# Solenoids.net
KiCad netlist of a schematic drawn in Altium Designer
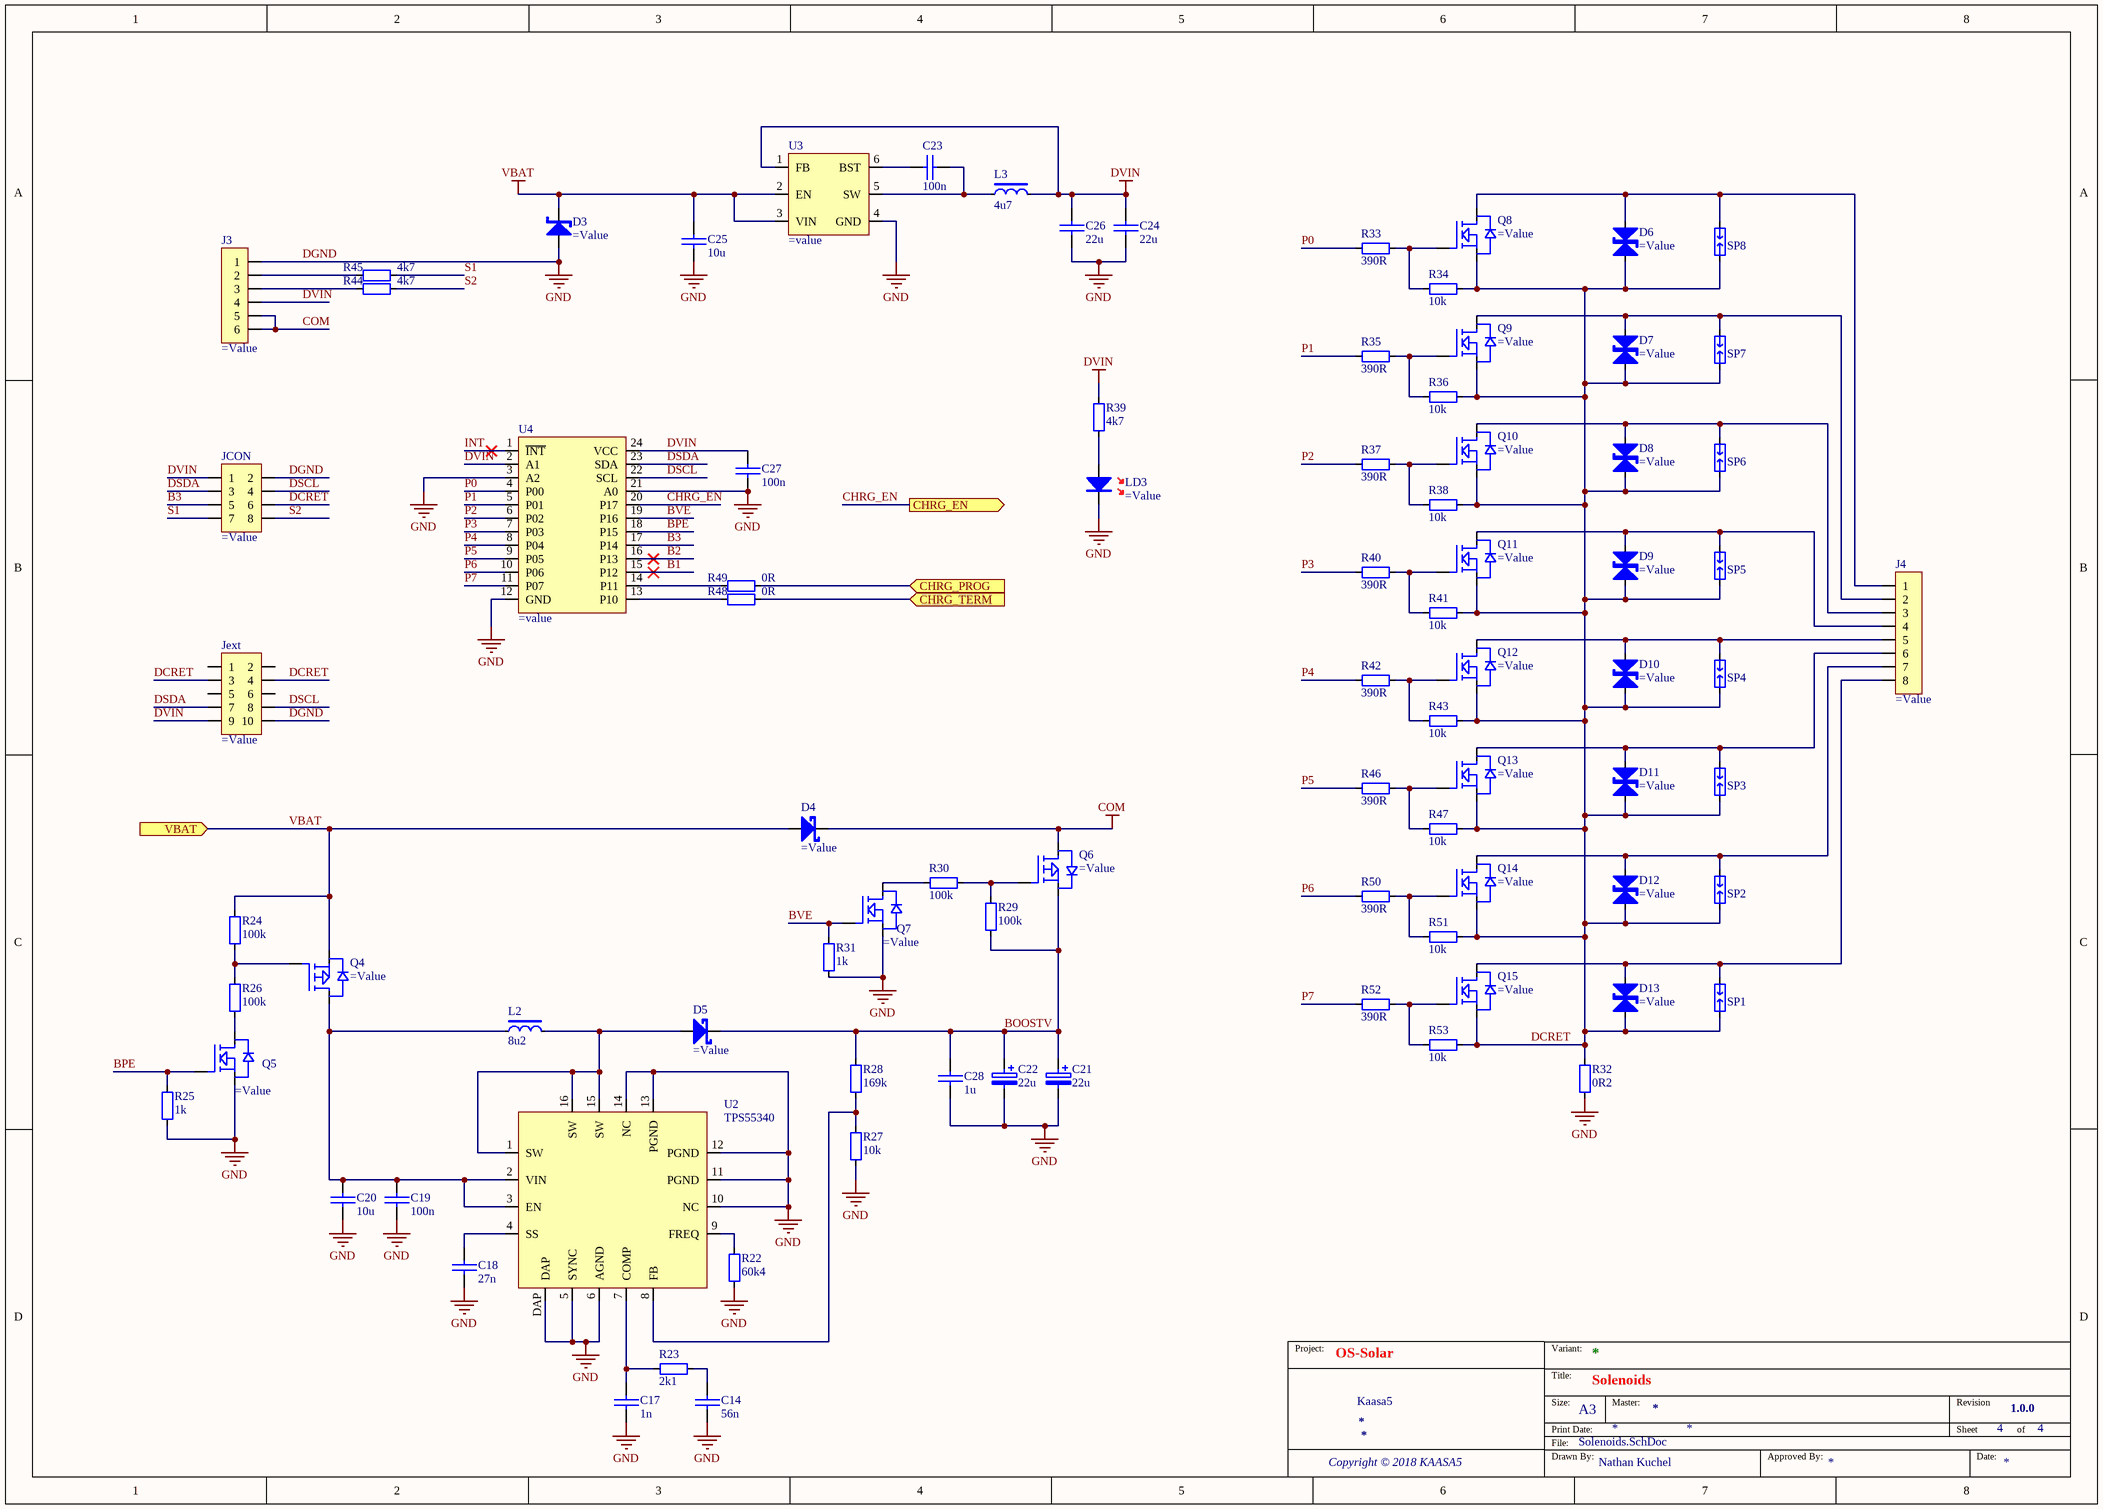
[diagram p0: Solenoids.SchDoc]

(export (version "E")
  (design (tool "Eeschema 10.0.6"))
  (components
    (comp (ref "C14")
      (value "56n")
      (footprint "CAPC1608X09N")
      (description "CAP SMD CER X7R 5% 50V 0603 (1608 Metric)")
      (fields (field (name "MANUFACTURER") "AVX Corporation") (field (name "PART NUMBER") "06035C563JAT2A"))
      (libsource (lib "kaasa5") (part "C_NORM"))
    )
    (comp (ref "C17")
      (value "1n")
      (footprint "CAPC1608X09N")
      (description "CAP SMD CER C0G/NPO 5% 50V 0603 (1608 Metric)")
      (fields (field (name "MANUFACTURER") "Yageo") (field (name "PART NUMBER") "CC0603JRNPO9BN102"))
      (libsource (lib "kaasa5") (part "C_NORM"))
    )
    (comp (ref "C18")
      (value "27n")
      (footprint "CAPC1608X09N")
      (description "CAP SMD CER X7R 5% 50V 0603 (1608 Metric)")
      (fields (field (name "MANUFACTURER") "Yageo") (field (name "PART NUMBER") "CC0603JRX7R9BB273"))
      (libsource (lib "kaasa5") (part "C_NORM"))
    )
    (comp (ref "C19")
      (value "100n")
      (footprint "CAPC1608X09N")
      (description "CAP SMD CER X7R 10% 50V 0603 (1608 Metric)")
      (fields (field (name "MANUFACTURER") "Yageo") (field (name "PART NUMBER") "CC0603KRX7R9BB104"))
      (libsource (lib "kaasa5") (part "C_NORM"))
    )
    (comp (ref "C20")
      (value "10u")
      (footprint "CAPC3216X18N")
      (description "CAP SMD CER X7R 10% 50V 1206 (3216 Metric)")
      (fields
        (field (name "MANUFACTURER") "Samsung Electro-Mechanics")
        (field (name "PART NUMBER") "CL31B106KBHNNNE")
      )
      (libsource (lib "kaasa5") (part "C_NORM"))
    )
    (comp (ref "C21")
      (value "22u")
      (footprint "CAPAE630X600")
      (description "CAP SMD ELECTRO 20% 35V SMAE")
      (fields
        (field (name "MANUFACTURER") "Panasonic Electronic Components")
        (field (name "PART NUMBER") "35SVPF22M")
      )
      (libsource (lib "kaasa5") (part "C_POL"))
    )
    (comp (ref "C22")
      (value "22u")
      (footprint "CAPAE630X600")
      (description "CAP SMD ELECTRO 20% 35V SMAE")
      (fields
        (field (name "MANUFACTURER") "Panasonic Electronic Components")
        (field (name "PART NUMBER") "35SVPF22M")
      )
      (libsource (lib "kaasa5") (part "C_POL"))
    )
    (comp (ref "C23")
      (value "100n")
      (footprint "CAPC1608X09N")
      (description "CAP SMD CER X7R 10% 50V 0603 (1608 Metric)")
      (fields (field (name "MANUFACTURER") "Yageo") (field (name "PART NUMBER") "CC0603KRX7R9BB104"))
      (libsource (lib "kaasa5") (part "C_NORM"))
    )
    (comp (ref "C24")
      (value "22u")
      (footprint "CAPC3216X18N")
      (description "CAP SMD CER X7R 10% 10V 1206 (3216 Metric)")
      (fields
        (field (name "MANUFACTURER") "Samsung Electro-Mechanics")
        (field (name "PART NUMBER") "CL31B226KPHNNNE")
      )
      (libsource (lib "kaasa5") (part "C_NORM"))
    )
    (comp (ref "C25")
      (value "10u")
      (footprint "CAPC3216X18N")
      (description "CAP SMD CER X7R 10% 50V 1206 (3216 Metric)")
      (fields
        (field (name "MANUFACTURER") "Samsung Electro-Mechanics")
        (field (name "PART NUMBER") "CL31B106KBHNNNE")
      )
      (libsource (lib "kaasa5") (part "C_NORM"))
    )
    (comp (ref "C26")
      (value "22u")
      (footprint "CAPC3216X18N")
      (description "CAP SMD CER X7R 10% 10V 1206 (3216 Metric)")
      (fields
        (field (name "MANUFACTURER") "Samsung Electro-Mechanics")
        (field (name "PART NUMBER") "CL31B226KPHNNNE")
      )
      (libsource (lib "kaasa5") (part "C_NORM"))
    )
    (comp (ref "C27")
      (value "100n")
      (footprint "CAPC1608X09N")
      (description "CAP SMD CER X7R 10% 50V 0603 (1608 Metric)")
      (fields (field (name "MANUFACTURER") "Yageo") (field (name "PART NUMBER") "CC0603KRX7R9BB104"))
      (libsource (lib "kaasa5") (part "C_NORM"))
    )
    (comp (ref "C28")
      (value "1u")
      (footprint "CAPC1608X09N")
      (description "CAP SMD CER X7R 10% 50V 0805 (2012 Metric)")
      (fields (field (name "MANUFACTURER") "Yageo") (field (name "PART NUMBER") "CC0805KKX7R9BB105"))
      (libsource (lib "kaasa5") (part "C_NORM"))
    )
    (comp (ref "D3")
      (value "~")
      (footprint "DIOSMBX25N")
      (description "DIODE SMD TVS 24V 600W SMB")
      (fields (field (name "MANUFACTURER") "Littelfuse Inc.") (field (name "PART NUMBER") "SMBJ24A"))
      (libsource (lib "kaasa5") (part "ZD_NORM"))
    )
    (comp (ref "D4")
      (value "~")
      (footprint "DIOSMCX25N")
      (description "DIODE SMD SCHOTTKY 40V 3A SMC")
      (fields (field (name "MANUFACTURER") "ON Semiconductor") (field (name "PART NUMBER") "MBRS340T3G"))
      (libsource (lib "kaasa5") (part "D_SCHOTTKY"))
    )
    (comp (ref "D5")
      (value "~")
      (footprint "DIOSMCX25N")
      (description "DIODE SMD SCHOTTKY 40V 3A SMC")
      (fields (field (name "MANUFACTURER") "ON Semiconductor") (field (name "PART NUMBER") "MBRS340T3G"))
      (libsource (lib "kaasa5") (part "D_SCHOTTKY"))
    )
    (comp (ref "D6")
      (value "~")
      (footprint "DIOSMBX25NB")
      (description "DIODE SMD TVS 24V 600W SMB")
      (fields (field (name "MANUFACTURER") "Littelfuse Inc.") (field (name "PART NUMBER") "SMBJ24CA"))
      (libsource (lib "kaasa5") (part "D_TRANSORB"))
    )
    (comp (ref "D7")
      (value "~")
      (footprint "DIOSMBX25NB")
      (description "DIODE SMD TVS 24V 600W SMB")
      (fields (field (name "MANUFACTURER") "Littelfuse Inc.") (field (name "PART NUMBER") "SMBJ24CA"))
      (libsource (lib "kaasa5") (part "D_TRANSORB"))
    )
    (comp (ref "D8")
      (value "~")
      (footprint "DIOSMBX25NB")
      (description "DIODE SMD TVS 24V 600W SMB")
      (fields (field (name "MANUFACTURER") "Littelfuse Inc.") (field (name "PART NUMBER") "SMBJ24CA"))
      (libsource (lib "kaasa5") (part "D_TRANSORB"))
    )
    (comp (ref "D9")
      (value "~")
      (footprint "DIOSMBX25NB")
      (description "DIODE SMD TVS 24V 600W SMB")
      (fields (field (name "MANUFACTURER") "Littelfuse Inc.") (field (name "PART NUMBER") "SMBJ24CA"))
      (libsource (lib "kaasa5") (part "D_TRANSORB"))
    )
    (comp (ref "D10")
      (value "~")
      (footprint "DIOSMBX25NB")
      (description "DIODE SMD TVS 24V 600W SMB")
      (fields (field (name "MANUFACTURER") "Littelfuse Inc.") (field (name "PART NUMBER") "SMBJ24CA"))
      (libsource (lib "kaasa5") (part "D_TRANSORB"))
    )
    (comp (ref "D11")
      (value "~")
      (footprint "DIOSMBX25NB")
      (description "DIODE SMD TVS 24V 600W SMB")
      (fields (field (name "MANUFACTURER") "Littelfuse Inc.") (field (name "PART NUMBER") "SMBJ24CA"))
      (libsource (lib "kaasa5") (part "D_TRANSORB"))
    )
    (comp (ref "D12")
      (value "~")
      (footprint "DIOSMBX25NB")
      (description "DIODE SMD TVS 24V 600W SMB")
      (fields (field (name "MANUFACTURER") "Littelfuse Inc.") (field (name "PART NUMBER") "SMBJ24CA"))
      (libsource (lib "kaasa5") (part "D_TRANSORB"))
    )
    (comp (ref "D13")
      (value "~")
      (footprint "DIOSMBX25NB")
      (description "DIODE SMD TVS 24V 600W SMB")
      (fields (field (name "MANUFACTURER") "Littelfuse Inc.") (field (name "PART NUMBER") "SMBJ24CA"))
      (libsource (lib "kaasa5") (part "D_TRANSORB"))
    )
    (comp (ref "J3")
      (value "~")
      (footprint "HDR1X6_350_RA")
      (description "CON THRU RIGHT ANGLE 8A 300V Header 1x6pin")
      (fields (field (name "MANUFACTURER") "Molex, LLC") (field (name "PART NUMBER") "0395021006"))
      (libsource (lib "kaasa5") (part "J_CON_SIL_6"))
    )
    (comp (ref "J4")
      (value "~")
      (footprint "HDR1X8_350_RA")
      (description "CON THRU RIGHT ANGLE 8A 300V Header 1x8pin")
      (fields (field (name "MANUFACTURER") "Molex, LLC") (field (name "PART NUMBER") "0395021008"))
      (libsource (lib "kaasa5") (part "J_CON_SIL_8"))
    )
    (comp (ref "JCON")
      (value "~")
      (footprint "HDR2X4")
      (description "CON THRU VERTICAL 0.100\" (2.54mm)  Header 2x4pin")
      (fields
        (field (name "MANUFACTURER") "Amphenol Commercial Products")
        (field (name "PART NUMBER") "68602-208HLF")
      )
      (libsource (lib "kaasa5") (part "J_CON_IDC_8"))
    )
    (comp (ref "Jext")
      (value "~")
      (footprint "HDR2X5RA")
      (description "CON THRU RIGHT ANGLE 2.54mm 3A 250V Header 2x5pin")
      (fields
        (field (name "MANUFACTURER") "Wurth Electronics Inc")
        (field (name "PART NUMBER") "61201021721")
      )
      (libsource (lib "kaasa5") (part "J_CON_IDC_10"))
    )
    (comp (ref "L2")
      (value "8u2")
      (footprint "INDP5553X51N")
      (description "IND SMD Shielded W/W 20% 60V 5.6A 31.75mOhm 5553")
      (fields (field (name "MANUFACTURER") "Coilcraft") (field (name "PART NUMBER") "XAL5050-822MEB"))
      (libsource (lib "") (part "L_FER_1"))
    )
    (comp (ref "L3")
      (value "4u7")
      (footprint "INDP3030X15N")
      (description "IND SMD Shielded W/W 20% 1.4A 167mOhm 3015")
      (fields (field (name "MANUFACTURER") "Coilcraft") (field (name "PART NUMBER") "EPL3015-472MLB"))
      (libsource (lib "kaasa5") (part "L_FER"))
    )
    (comp (ref "LD3")
      (value "~")
      (footprint "LEDC1608X06N-RED")
      (description "LED SMD RED 180mcd Max 0603 (1608 Metric)")
      (fields (field (name "MANUFACTURER") "Lite-On Inc.") (field (name "PART NUMBER") "LTST-C191KRKT"))
      (libsource (lib "kaasa5") (part "LED_NORM_RED"))
    )
    (comp (ref "Q4")
      (value "~")
      (footprint "SOT95P230X110-3N")
      (description "TRANS MOSFET P-Channel -30V -4.3A 70mOhm SOT23")
      (fields (field (name "MANUFACTURER") "Diodes Incorporated") (field (name "PART NUMBER") "DMP3056L-7"))
      (libsource (lib "kaasa5") (part "Q_MOSFET_P_E"))
    )
    (comp (ref "Q5")
      (value "~")
      (footprint "SOT95P230X110-3N")
      (description "TRANS MOSFET N-Channel 60V 360mA SOT23")
      (fields (field (name "MANUFACTURER") "Nexperia USA Inc.") (field (name "PART NUMBER") "2N7002P,235"))
      (libsource (lib "kaasa5") (part "Q_MOSFET_N_E"))
    )
    (comp (ref "Q6")
      (value "~")
      (footprint "SOT95P230X110-3N")
      (description "TRANS MOSFET P-Channel -30V -4.3A 70mOhm SOT23")
      (fields (field (name "MANUFACTURER") "Diodes Incorporated") (field (name "PART NUMBER") "DMP3056L-7"))
      (libsource (lib "kaasa5") (part "Q_MOSFET_P_E"))
    )
    (comp (ref "Q7")
      (value "~")
      (footprint "SOT95P230X110-3N")
      (description "TRANS MOSFET N-Channel 60V 360mA SOT23")
      (fields (field (name "MANUFACTURER") "Nexperia USA Inc.") (field (name "PART NUMBER") "2N7002P,235"))
      (libsource (lib "kaasa5") (part "Q_MOSFET_N_E"))
    )
    (comp (ref "Q8")
      (value "~")
      (footprint "SOT95P230X110-3N")
      (description "TRANS MOSFET N-Channel 30V 5.6A 32mOhm SOT23")
      (fields (field (name "MANUFACTURER") "Diodes Incorporated") (field (name "PART NUMBER") "DMN3042L-7"))
      (libsource (lib "kaasa5") (part "Q_MOSFET_N_E"))
    )
    (comp (ref "Q9")
      (value "~")
      (footprint "SOT95P230X110-3N")
      (description "TRANS MOSFET N-Channel 30V 5.6A 32mOhm SOT23")
      (fields (field (name "MANUFACTURER") "Diodes Incorporated") (field (name "PART NUMBER") "DMN3042L-7"))
      (libsource (lib "kaasa5") (part "Q_MOSFET_N_E"))
    )
    (comp (ref "Q10")
      (value "~")
      (footprint "SOT95P230X110-3N")
      (description "TRANS MOSFET N-Channel 30V 5.6A 32mOhm SOT23")
      (fields (field (name "MANUFACTURER") "Diodes Incorporated") (field (name "PART NUMBER") "DMN3042L-7"))
      (libsource (lib "kaasa5") (part "Q_MOSFET_N_E"))
    )
    (comp (ref "Q11")
      (value "~")
      (footprint "SOT95P230X110-3N")
      (description "TRANS MOSFET N-Channel 30V 5.6A 32mOhm SOT23")
      (fields (field (name "MANUFACTURER") "Diodes Incorporated") (field (name "PART NUMBER") "DMN3042L-7"))
      (libsource (lib "kaasa5") (part "Q_MOSFET_N_E"))
    )
    (comp (ref "Q12")
      (value "~")
      (footprint "SOT95P230X110-3N")
      (description "TRANS MOSFET N-Channel 30V 5.6A 32mOhm SOT23")
      (fields (field (name "MANUFACTURER") "Diodes Incorporated") (field (name "PART NUMBER") "DMN3042L-7"))
      (libsource (lib "kaasa5") (part "Q_MOSFET_N_E"))
    )
    (comp (ref "Q13")
      (value "~")
      (footprint "SOT95P230X110-3N")
      (description "TRANS MOSFET N-Channel 30V 5.6A 32mOhm SOT23")
      (fields (field (name "MANUFACTURER") "Diodes Incorporated") (field (name "PART NUMBER") "DMN3042L-7"))
      (libsource (lib "kaasa5") (part "Q_MOSFET_N_E"))
    )
    (comp (ref "Q14")
      (value "~")
      (footprint "SOT95P230X110-3N")
      (description "TRANS MOSFET N-Channel 30V 5.6A 32mOhm SOT23")
      (fields (field (name "MANUFACTURER") "Diodes Incorporated") (field (name "PART NUMBER") "DMN3042L-7"))
      (libsource (lib "kaasa5") (part "Q_MOSFET_N_E"))
    )
    (comp (ref "Q15")
      (value "~")
      (footprint "SOT95P230X110-3N")
      (description "TRANS MOSFET N-Channel 30V 5.6A 32mOhm SOT23")
      (fields (field (name "MANUFACTURER") "Diodes Incorporated") (field (name "PART NUMBER") "DMN3042L-7"))
      (libsource (lib "kaasa5") (part "Q_MOSFET_N_E"))
    )
    (comp (ref "R22")
      (value "60k4")
      (footprint "RESC1608X06N")
      (description "RES SMD Think Film 1% 1/10W 150V 0603 (1608 Metric)")
      (fields (field (name "MANUFACTURER") "Yageo") (field (name "PART NUMBER") "RC0603FR-0760K4L"))
      (libsource (lib "kaasa5") (part "R_NORM"))
    )
    (comp (ref "R23")
      (value "2k1")
      (footprint "RESC1608X06N")
      (description "RES SMD Think Film 1% 1/10W 150V 0603 (1608 Metric)")
      (fields (field (name "MANUFACTURER") "Yageo") (field (name "PART NUMBER") "RC0603FR-072K1L"))
      (libsource (lib "kaasa5") (part "R_NORM"))
    )
    (comp (ref "R24")
      (value "100k")
      (footprint "RESC1608X06N")
      (description "RES SMD Think Film 1% 1/10W 150V 0603 (1608 Metric)")
      (fields (field (name "MANUFACTURER") "Yageo") (field (name "PART NUMBER") "RC0603FR-07100KL"))
      (libsource (lib "kaasa5") (part "R_NORM"))
    )
    (comp (ref "R25")
      (value "1k")
      (footprint "RESC1608X06N")
      (description "RES SMD Think Film 1% 1/10W 150V 0603 (1608 Metric)")
      (fields (field (name "MANUFACTURER") "Yageo") (field (name "PART NUMBER") "RC0603FR-071KL"))
      (libsource (lib "kaasa5") (part "R_NORM"))
    )
    (comp (ref "R26")
      (value "100k")
      (footprint "RESC1608X06N")
      (description "RES SMD Think Film 1% 1/10W 150V 0603 (1608 Metric)")
      (fields (field (name "MANUFACTURER") "Yageo") (field (name "PART NUMBER") "RC0603FR-07100KL"))
      (libsource (lib "kaasa5") (part "R_NORM"))
    )
    (comp (ref "R27")
      (value "10k")
      (footprint "RESC1608X06N")
      (description "RES SMD Think Film 1% 1/10W 150V 0603 (1608 Metric)")
      (fields (field (name "MANUFACTURER") "Yageo") (field (name "PART NUMBER") "RC0603FR-0710KL"))
      (libsource (lib "kaasa5") (part "R_NORM"))
    )
    (comp (ref "R28")
      (value "169k")
      (footprint "RESC1608X06N")
      (description "RES SMD Think Film 1% 1/10W 150V 0603 (1608 Metric)")
      (fields (field (name "MANUFACTURER") "Yageo") (field (name "PART NUMBER") "RC0603FR-07169KL"))
      (libsource (lib "kaasa5") (part "R_NORM"))
    )
    (comp (ref "R29")
      (value "100k")
      (footprint "RESC1608X06N")
      (description "RES SMD Think Film 1% 1/10W 150V 0603 (1608 Metric)")
      (fields (field (name "MANUFACTURER") "Yageo") (field (name "PART NUMBER") "RC0603FR-07100KL"))
      (libsource (lib "kaasa5") (part "R_NORM"))
    )
    (comp (ref "R30")
      (value "100k")
      (footprint "RESC1608X06N")
      (description "RES SMD Think Film 1% 1/10W 150V 0603 (1608 Metric)")
      (fields (field (name "MANUFACTURER") "Yageo") (field (name "PART NUMBER") "RC0603FR-07100KL"))
      (libsource (lib "kaasa5") (part "R_NORM"))
    )
    (comp (ref "R31")
      (value "1k")
      (footprint "RESC1608X06N")
      (description "RES SMD Think Film 1% 1/10W 150V 0603 (1608 Metric)")
      (fields (field (name "MANUFACTURER") "Yageo") (field (name "PART NUMBER") "RC0603FR-071KL"))
      (libsource (lib "kaasa5") (part "R_NORM"))
    )
    (comp (ref "R32")
      (value "0R2")
      (footprint "RESC5025X06N")
      (description "RES SMD Metal Strip 1% 1/2W 75ppm/degC 2010 (5025 Metric)")
      (fields (field (name "MANUFACTURER") "Vishay Dale") (field (name "PART NUMBER") "WSL2010R2000FEA"))
      (libsource (lib "kaasa5") (part "R_NORM"))
    )
    (comp (ref "R33")
      (value "390R")
      (footprint "RESC1608X06N")
      (description "RES SMD Think Film 1% 1/10W 150V 0603 (1608 Metric)")
      (fields (field (name "MANUFACTURER") "Yageo") (field (name "PART NUMBER") "RC0603FR-07390RL"))
      (libsource (lib "kaasa5") (part "R_NORM"))
    )
    (comp (ref "R34")
      (value "10k")
      (footprint "RESC1608X06N")
      (description "RES SMD Think Film 1% 1/10W 150V 0603 (1608 Metric)")
      (fields (field (name "MANUFACTURER") "Yageo") (field (name "PART NUMBER") "RC0603FR-0710KL"))
      (libsource (lib "kaasa5") (part "R_NORM"))
    )
    (comp (ref "R35")
      (value "390R")
      (footprint "RESC1608X06N")
      (description "RES SMD Think Film 1% 1/10W 150V 0603 (1608 Metric)")
      (fields (field (name "MANUFACTURER") "Yageo") (field (name "PART NUMBER") "RC0603FR-07390RL"))
      (libsource (lib "kaasa5") (part "R_NORM"))
    )
    (comp (ref "R36")
      (value "10k")
      (footprint "RESC1608X06N")
      (description "RES SMD Think Film 1% 1/10W 150V 0603 (1608 Metric)")
      (fields (field (name "MANUFACTURER") "Yageo") (field (name "PART NUMBER") "RC0603FR-0710KL"))
      (libsource (lib "kaasa5") (part "R_NORM"))
    )
    (comp (ref "R37")
      (value "390R")
      (footprint "RESC1608X06N")
      (description "RES SMD Think Film 1% 1/10W 150V 0603 (1608 Metric)")
      (fields (field (name "MANUFACTURER") "Yageo") (field (name "PART NUMBER") "RC0603FR-07390RL"))
      (libsource (lib "kaasa5") (part "R_NORM"))
    )
    (comp (ref "R38")
      (value "10k")
      (footprint "RESC1608X06N")
      (description "RES SMD Think Film 1% 1/10W 150V 0603 (1608 Metric)")
      (fields (field (name "MANUFACTURER") "Yageo") (field (name "PART NUMBER") "RC0603FR-0710KL"))
      (libsource (lib "kaasa5") (part "R_NORM"))
    )
    (comp (ref "R39")
      (value "4k7")
      (footprint "RESC1608X06N")
      (description "RES SMD Think Film 1% 1/10W 150V 0603 (1608 Metric)")
      (fields (field (name "MANUFACTURER") "Yageo") (field (name "PART NUMBER") "RC0603FR-074K7L"))
      (libsource (lib "kaasa5") (part "R_NORM"))
    )
    (comp (ref "R40")
      (value "390R")
      (footprint "RESC1608X06N")
      (description "RES SMD Think Film 1% 1/10W 150V 0603 (1608 Metric)")
      (fields (field (name "MANUFACTURER") "Yageo") (field (name "PART NUMBER") "RC0603FR-07390RL"))
      (libsource (lib "kaasa5") (part "R_NORM"))
    )
    (comp (ref "R41")
      (value "10k")
      (footprint "RESC1608X06N")
      (description "RES SMD Think Film 1% 1/10W 150V 0603 (1608 Metric)")
      (fields (field (name "MANUFACTURER") "Yageo") (field (name "PART NUMBER") "RC0603FR-0710KL"))
      (libsource (lib "kaasa5") (part "R_NORM"))
    )
    (comp (ref "R42")
      (value "390R")
      (footprint "RESC1608X06N")
      (description "RES SMD Think Film 1% 1/10W 150V 0603 (1608 Metric)")
      (fields (field (name "MANUFACTURER") "Yageo") (field (name "PART NUMBER") "RC0603FR-07390RL"))
      (libsource (lib "kaasa5") (part "R_NORM"))
    )
    (comp (ref "R43")
      (value "10k")
      (footprint "RESC1608X06N")
      (description "RES SMD Think Film 1% 1/10W 150V 0603 (1608 Metric)")
      (fields (field (name "MANUFACTURER") "Yageo") (field (name "PART NUMBER") "RC0603FR-0710KL"))
      (libsource (lib "kaasa5") (part "R_NORM"))
    )
    (comp (ref "R44")
      (value "4k7")
      (footprint "RESC1608X06N")
      (description "RES SMD Think Film 1% 1/10W 150V 0603 (1608 Metric)")
      (fields (field (name "MANUFACTURER") "Yageo") (field (name "PART NUMBER") "RC0603FR-074K7L"))
      (libsource (lib "kaasa5") (part "R_NORM"))
    )
    (comp (ref "R45")
      (value "4k7")
      (footprint "RESC1608X06N")
      (description "RES SMD Think Film 1% 1/10W 150V 0603 (1608 Metric)")
      (fields (field (name "MANUFACTURER") "Yageo") (field (name "PART NUMBER") "RC0603FR-074K7L"))
      (libsource (lib "kaasa5") (part "R_NORM"))
    )
    (comp (ref "R46")
      (value "390R")
      (footprint "RESC1608X06N")
      (description "RES SMD Think Film 1% 1/10W 150V 0603 (1608 Metric)")
      (fields (field (name "MANUFACTURER") "Yageo") (field (name "PART NUMBER") "RC0603FR-07390RL"))
      (libsource (lib "kaasa5") (part "R_NORM"))
    )
    (comp (ref "R47")
      (value "10k")
      (footprint "RESC1608X06N")
      (description "RES SMD Think Film 1% 1/10W 150V 0603 (1608 Metric)")
      (fields (field (name "MANUFACTURER") "Yageo") (field (name "PART NUMBER") "RC0603FR-0710KL"))
      (libsource (lib "kaasa5") (part "R_NORM"))
    )
    (comp (ref "R48")
      (value "0R")
      (footprint "RESC1608X06N")
      (description "RES SMD Think Film 1% 1/10W 1A 0603 (1608 Metric)")
      (fields (field (name "MANUFACTURER") "Yageo") (field (name "PART NUMBER") "RC0603FR-070RL"))
      (libsource (lib "kaasa5") (part "R_NORM"))
    )
    (comp (ref "R49")
      (value "0R")
      (footprint "RESC1608X06N")
      (description "RES SMD Think Film 1% 1/10W 1A 0603 (1608 Metric)")
      (fields (field (name "MANUFACTURER") "Yageo") (field (name "PART NUMBER") "RC0603FR-070RL"))
      (libsource (lib "kaasa5") (part "R_NORM"))
    )
    (comp (ref "R50")
      (value "390R")
      (footprint "RESC1608X06N")
      (description "RES SMD Think Film 1% 1/10W 150V 0603 (1608 Metric)")
      (fields (field (name "MANUFACTURER") "Yageo") (field (name "PART NUMBER") "RC0603FR-07390RL"))
      (libsource (lib "kaasa5") (part "R_NORM"))
    )
    (comp (ref "R51")
      (value "10k")
      (footprint "RESC1608X06N")
      (description "RES SMD Think Film 1% 1/10W 150V 0603 (1608 Metric)")
      (fields (field (name "MANUFACTURER") "Yageo") (field (name "PART NUMBER") "RC0603FR-0710KL"))
      (libsource (lib "kaasa5") (part "R_NORM"))
    )
    (comp (ref "R52")
      (value "390R")
      (footprint "RESC1608X06N")
      (description "RES SMD Think Film 1% 1/10W 150V 0603 (1608 Metric)")
      (fields (field (name "MANUFACTURER") "Yageo") (field (name "PART NUMBER") "RC0603FR-07390RL"))
      (libsource (lib "kaasa5") (part "R_NORM"))
    )
    (comp (ref "R53")
      (value "10k")
      (footprint "RESC1608X06N")
      (description "RES SMD Think Film 1% 1/10W 150V 0603 (1608 Metric)")
      (fields (field (name "MANUFACTURER") "Yageo") (field (name "PART NUMBER") "RC0603FR-0710KL"))
      (libsource (lib "kaasa5") (part "R_NORM"))
    )
    (comp (ref "SP1")
      (value "0.15mm")
      (footprint "SPGAP-15")
      (description "SPARK GAP 1kV PCB")
      (fields (field (name "MANUFACTURER") "n/a"))
      (libsource (lib "kaasa5") (part "SP_NORM"))
    )
    (comp (ref "SP2")
      (value "0.15mm")
      (footprint "SPGAP-15")
      (description "SPARK GAP 1kV PCB")
      (fields (field (name "MANUFACTURER") "n/a"))
      (libsource (lib "kaasa5") (part "SP_NORM"))
    )
    (comp (ref "SP3")
      (value "0.15mm")
      (footprint "SPGAP-15")
      (description "SPARK GAP 1kV PCB")
      (fields (field (name "MANUFACTURER") "n/a"))
      (libsource (lib "kaasa5") (part "SP_NORM"))
    )
    (comp (ref "SP4")
      (value "0.15mm")
      (footprint "SPGAP-15")
      (description "SPARK GAP 1kV PCB")
      (fields (field (name "MANUFACTURER") "n/a"))
      (libsource (lib "kaasa5") (part "SP_NORM"))
    )
    (comp (ref "SP5")
      (value "0.15mm")
      (footprint "SPGAP-15")
      (description "SPARK GAP 1kV PCB")
      (fields (field (name "MANUFACTURER") "n/a"))
      (libsource (lib "kaasa5") (part "SP_NORM"))
    )
    (comp (ref "SP6")
      (value "0.15mm")
      (footprint "SPGAP-15")
      (description "SPARK GAP 1kV PCB")
      (fields (field (name "MANUFACTURER") "n/a"))
      (libsource (lib "kaasa5") (part "SP_NORM"))
    )
    (comp (ref "SP7")
      (value "0.15mm")
      (footprint "SPGAP-15")
      (description "SPARK GAP 1kV PCB")
      (fields (field (name "MANUFACTURER") "n/a"))
      (libsource (lib "kaasa5") (part "SP_NORM"))
    )
    (comp (ref "SP8")
      (value "0.15mm")
      (footprint "SPGAP-15")
      (description "SPARK GAP 1kV PCB")
      (fields (field (name "MANUFACTURER") "n/a"))
      (libsource (lib "kaasa5") (part "SP_NORM"))
    )
    (comp (ref "U2")
      (value "TPS55340")
      (footprint "QFN50P350X350X90-16N")
      (description "IC SMD SYNC BOOST CONV 5.25A QFN16")
      (fields (field (name "MANUFACTURER") "Texas Instruments") (field (name "PART NUMBER") "TPS55340RTER"))
      (libsource (lib "kaasa5") (part "TPS55340"))
    )
    (comp (ref "U3")
      (value "~")
      (footprint "SOT95P280X125-6N")
      (description "IC SMD SYNC BUCK CONV 5V 2A TSOT-23-6")
      (fields (field (name "MANUFACTURER") "Diodes Incorporated") (field (name "PART NUMBER") "AP63205WU-7"))
      (libsource (lib "kaasa5") (part "AP6320X"))
    )
    (comp (ref "U4")
      (value "~")
      (footprint "TSOP65P640X120-24N")
      (description "IC SMD I/O EXPANDER 16-BIT I2C TSSOP-24")
      (fields
        (field (name "MANUFACTURER") "NXP Semiconductors")
        (field (name "PART NUMBER") "PCA9555APW,118")
      )
      (libsource (lib "kaasa5") (part "PCF8575"))
    )
  )
  (nets
    (net (code "1") (name "/B1") (class "Default")
      (node (ref "U4") (pin "15") (pinfunction "P12_15") (pintype "passive"))
    )
    (net (code "2") (name "/B2") (class "Default")
      (node (ref "U4") (pin "16") (pinfunction "P13_16") (pintype "passive"))
    )
    (net (code "3") (name "/B3") (class "Default")
      (node (ref "JCON") (pin "5") (pinfunction "5_5") (pintype "passive"))
      (node (ref "U4") (pin "17") (pinfunction "P14_17") (pintype "passive"))
    )
    (net (code "4") (name "/BOOSTV") (class "Default")
      (node (ref "C21") (pin "1") (pintype "passive"))
      (node (ref "C22") (pin "1") (pintype "passive"))
      (node (ref "C28") (pin "1") (pintype "passive"))
      (node (ref "D5") (pin "2") (pinfunction "K_2") (pintype "passive"))
      (node (ref "Q6") (pin "2") (pinfunction "S_2") (pintype "passive"))
      (node (ref "R28") (pin "2") (pintype "passive"))
      (node (ref "R29") (pin "1") (pintype "passive"))
    )
    (net (code "5") (name "/BPE") (class "Default")
      (node (ref "Q5") (pin "1") (pinfunction "G_1") (pintype "passive"))
      (node (ref "R25") (pin "2") (pintype "passive"))
      (node (ref "U4") (pin "18") (pinfunction "P15_18") (pintype "passive"))
    )
    (net (code "6") (name "/BVE") (class "Default")
      (node (ref "Q7") (pin "1") (pinfunction "G_1") (pintype "passive"))
      (node (ref "R31") (pin "2") (pintype "passive"))
      (node (ref "U4") (pin "19") (pinfunction "P16_19") (pintype "passive"))
    )
    (net (code "7") (name "/CHRG_EN") (class "Default")
      (node (ref "U4") (pin "20") (pinfunction "P17_20") (pintype "passive"))
    )
    (net (code "8") (name "/CHRG_PROG") (class "Default") (node (ref "R49") (pin "2") (pintype "passive")))
    (net (code "9") (name "/CHRG_TERM") (class "Default") (node (ref "R48") (pin "2") (pintype "passive")))
    (net (code "10") (name "/DCRET") (class "Default")
      (node (ref "D10") (pin "1") (pinfunction "A1_1") (pintype "passive"))
      (node (ref "D11") (pin "1") (pinfunction "A1_1") (pintype "passive"))
      (node (ref "D12") (pin "1") (pinfunction "A1_1") (pintype "passive"))
      (node (ref "D13") (pin "1") (pinfunction "A1_1") (pintype "passive"))
      (node (ref "D6") (pin "1") (pinfunction "A1_1") (pintype "passive"))
      (node (ref "D7") (pin "1") (pinfunction "A1_1") (pintype "passive"))
      (node (ref "D8") (pin "1") (pinfunction "A1_1") (pintype "passive"))
      (node (ref "D9") (pin "1") (pinfunction "A1_1") (pintype "passive"))
      (node (ref "JCON") (pin "6") (pinfunction "6_6") (pintype "passive"))
      (node (ref "Jext") (pin "3") (pinfunction "3_3") (pintype "passive"))
      (node (ref "Jext") (pin "4") (pinfunction "4_4") (pintype "passive"))
      (node (ref "Q10") (pin "2") (pinfunction "S_2") (pintype "passive"))
      (node (ref "Q11") (pin "2") (pinfunction "S_2") (pintype "passive"))
      (node (ref "Q12") (pin "2") (pinfunction "S_2") (pintype "passive"))
      (node (ref "Q13") (pin "2") (pinfunction "S_2") (pintype "passive"))
      (node (ref "Q14") (pin "2") (pinfunction "S_2") (pintype "passive"))
      (node (ref "Q15") (pin "2") (pinfunction "S_2") (pintype "passive"))
      (node (ref "Q8") (pin "2") (pinfunction "S_2") (pintype "passive"))
      (node (ref "Q9") (pin "2") (pinfunction "S_2") (pintype "passive"))
      (node (ref "R32") (pin "2") (pintype "passive"))
      (node (ref "R34") (pin "2") (pintype "passive"))
      (node (ref "R36") (pin "2") (pintype "passive"))
      (node (ref "R38") (pin "2") (pintype "passive"))
      (node (ref "R41") (pin "2") (pintype "passive"))
      (node (ref "R43") (pin "2") (pintype "passive"))
      (node (ref "R47") (pin "2") (pintype "passive"))
      (node (ref "R51") (pin "2") (pintype "passive"))
      (node (ref "R53") (pin "2") (pintype "passive"))
      (node (ref "SP1") (pin "1") (pintype "passive"))
      (node (ref "SP2") (pin "1") (pintype "passive"))
      (node (ref "SP3") (pin "1") (pintype "passive"))
      (node (ref "SP4") (pin "1") (pintype "passive"))
      (node (ref "SP5") (pin "1") (pintype "passive"))
      (node (ref "SP6") (pin "1") (pintype "passive"))
      (node (ref "SP7") (pin "1") (pintype "passive"))
      (node (ref "SP8") (pin "1") (pintype "passive"))
    )
    (net (code "11") (name "/DSCL") (class "Default")
      (node (ref "JCON") (pin "4") (pinfunction "4_4") (pintype "passive"))
      (node (ref "Jext") (pin "8") (pinfunction "8_8") (pintype "passive"))
      (node (ref "U4") (pin "22") (pinfunction "SCL_22") (pintype "passive"))
    )
    (net (code "12") (name "/DSDA") (class "Default")
      (node (ref "JCON") (pin "3") (pinfunction "3_3") (pintype "passive"))
      (node (ref "Jext") (pin "7") (pinfunction "7_7") (pintype "passive"))
      (node (ref "U4") (pin "23") (pinfunction "SDA_23") (pintype "passive"))
    )
    (net (code "13") (name "/INT") (class "Default")
      (node (ref "U4") (pin "1") (pinfunction "~{INT}_1") (pintype "passive"))
    )
    (net (code "14") (name "/P0") (class "Default")
      (node (ref "R33") (pin "1") (pintype "passive"))
      (node (ref "U4") (pin "4") (pinfunction "P00_4") (pintype "passive"))
    )
    (net (code "15") (name "/P1") (class "Default")
      (node (ref "R35") (pin "1") (pintype "passive"))
      (node (ref "U4") (pin "5") (pinfunction "P01_5") (pintype "passive"))
    )
    (net (code "16") (name "/P2") (class "Default")
      (node (ref "R37") (pin "1") (pintype "passive"))
      (node (ref "U4") (pin "6") (pinfunction "P02_6") (pintype "passive"))
    )
    (net (code "17") (name "/P3") (class "Default")
      (node (ref "R40") (pin "1") (pintype "passive"))
      (node (ref "U4") (pin "7") (pinfunction "P03_7") (pintype "passive"))
    )
    (net (code "18") (name "/P4") (class "Default")
      (node (ref "R42") (pin "1") (pintype "passive"))
      (node (ref "U4") (pin "8") (pinfunction "P04_8") (pintype "passive"))
    )
    (net (code "19") (name "/P5") (class "Default")
      (node (ref "R46") (pin "1") (pintype "passive"))
      (node (ref "U4") (pin "9") (pinfunction "P05_9") (pintype "passive"))
    )
    (net (code "20") (name "/P6") (class "Default")
      (node (ref "R50") (pin "1") (pintype "passive"))
      (node (ref "U4") (pin "10") (pinfunction "P06_10") (pintype "passive"))
    )
    (net (code "21") (name "/P7") (class "Default")
      (node (ref "R52") (pin "1") (pintype "passive"))
      (node (ref "U4") (pin "11") (pinfunction "P07_11") (pintype "passive"))
    )
    (net (code "22") (name "/S1") (class "Default")
      (node (ref "JCON") (pin "7") (pinfunction "7_7") (pintype "passive"))
      (node (ref "R45") (pin "1") (pintype "passive"))
    )
    (net (code "23") (name "/S2") (class "Default")
      (node (ref "JCON") (pin "8") (pinfunction "8_8") (pintype "passive"))
      (node (ref "R44") (pin "1") (pintype "passive"))
    )
    (net (code "24") (name "COM") (class "Default")
      (node (ref "D4") (pin "2") (pinfunction "K_2") (pintype "passive"))
      (node (ref "J3") (pin "5") (pinfunction "5_5") (pintype "passive"))
      (node (ref "J3") (pin "6") (pinfunction "6_6") (pintype "passive"))
      (node (ref "Q6") (pin "3") (pinfunction "D_3") (pintype "passive"))
    )
    (net (code "25") (name "DVIN") (class "Default")
      (node (ref "C24") (pin "1") (pintype "passive"))
      (node (ref "C26") (pin "1") (pintype "passive"))
      (node (ref "C27") (pin "1") (pintype "passive"))
      (node (ref "J3") (pin "4") (pinfunction "4_4") (pintype "passive"))
      (node (ref "JCON") (pin "1") (pinfunction "1_1") (pintype "passive"))
      (node (ref "Jext") (pin "9") (pinfunction "9_9") (pintype "passive"))
      (node (ref "L3") (pin "2") (pintype "passive"))
      (node (ref "R39") (pin "2") (pintype "passive"))
      (node (ref "U3") (pin "1") (pinfunction "FB_1") (pintype "passive"))
      (node (ref "U4") (pin "2") (pinfunction "A1_2") (pintype "passive"))
      (node (ref "U4") (pin "24") (pinfunction "VCC_24") (pintype "passive"))
    )
    (net (code "26") (name "GND") (class "Default")
      (node (ref "C14") (pin "2") (pintype "passive"))
      (node (ref "C17") (pin "2") (pintype "passive"))
      (node (ref "C18") (pin "2") (pintype "passive"))
      (node (ref "C19") (pin "2") (pintype "passive"))
      (node (ref "C20") (pin "2") (pintype "passive"))
      (node (ref "C21") (pin "2") (pintype "passive"))
      (node (ref "C22") (pin "2") (pintype "passive"))
      (node (ref "C24") (pin "2") (pintype "passive"))
      (node (ref "C25") (pin "2") (pintype "passive"))
      (node (ref "C26") (pin "2") (pintype "passive"))
      (node (ref "C27") (pin "2") (pintype "passive"))
      (node (ref "C28") (pin "2") (pintype "passive"))
      (node (ref "D3") (pin "1") (pinfunction "A_1") (pintype "passive"))
      (node (ref "J3") (pin "1") (pinfunction "1_1") (pintype "passive"))
      (node (ref "JCON") (pin "2") (pinfunction "2_2") (pintype "passive"))
      (node (ref "Jext") (pin "10") (pinfunction "10_10") (pintype "passive"))
      (node (ref "LD3") (pin "2") (pinfunction "K_2") (pintype "passive"))
      (node (ref "Q5") (pin "2") (pinfunction "S_2") (pintype "passive"))
      (node (ref "Q7") (pin "2") (pinfunction "S_2") (pintype "passive"))
      (node (ref "R22") (pin "1") (pintype "passive"))
      (node (ref "R25") (pin "1") (pintype "passive"))
      (node (ref "R27") (pin "1") (pintype "passive"))
      (node (ref "R31") (pin "1") (pintype "passive"))
      (node (ref "R32") (pin "1") (pintype "passive"))
      (node (ref "U2") (pin "10") (pinfunction "NC_10") (pintype "passive"))
      (node (ref "U2") (pin "11") (pinfunction "PGND_11") (pintype "passive"))
      (node (ref "U2") (pin "12") (pinfunction "PGND_12") (pintype "passive"))
      (node (ref "U2") (pin "13") (pinfunction "PGND_13") (pintype "passive"))
      (node (ref "U2") (pin "14") (pinfunction "NC_14") (pintype "passive"))
      (node (ref "U2") (pin "5") (pinfunction "SYNC_5") (pintype "passive"))
      (node (ref "U2") (pin "6") (pinfunction "AGND_6") (pintype "passive"))
      (node (ref "U2") (pin "DAP") (pinfunction "DAP_DAP") (pintype "passive"))
      (node (ref "U3") (pin "4") (pinfunction "GND_4") (pintype "passive"))
      (node (ref "U4") (pin "12") (pinfunction "GND_12") (pintype "passive"))
      (node (ref "U4") (pin "21") (pinfunction "A0_21") (pintype "passive"))
      (node (ref "U4") (pin "3") (pinfunction "A2_3") (pintype "passive"))
    )
    (net (code "27") (name "Net-(C14-Pad1)") (class "Default")
      (node (ref "C14") (pin "1") (pintype "passive"))
      (node (ref "R23") (pin "1") (pintype "passive"))
    )
    (net (code "28") (name "Net-(D5-A)") (class "Default")
      (node (ref "D5") (pin "1") (pinfunction "A_1") (pintype "passive"))
      (node (ref "L2") (pin "1") (pintype "passive"))
      (node (ref "U2") (pin "1") (pinfunction "SW_1") (pintype "passive"))
      (node (ref "U2") (pin "15") (pinfunction "SW_15") (pintype "passive"))
      (node (ref "U2") (pin "16") (pinfunction "SW_16") (pintype "passive"))
    )
    (net (code "29") (name "Net-(D6-A2)") (class "Default")
      (node (ref "D6") (pin "2") (pinfunction "A2_2") (pintype "passive"))
      (node (ref "J4") (pin "1") (pinfunction "1_1") (pintype "passive"))
      (node (ref "Q8") (pin "3") (pinfunction "D_3") (pintype "passive"))
      (node (ref "SP8") (pin "2") (pintype "passive"))
    )
    (net (code "30") (name "Net-(D7-A2)") (class "Default")
      (node (ref "D7") (pin "2") (pinfunction "A2_2") (pintype "passive"))
      (node (ref "J4") (pin "2") (pinfunction "2_2") (pintype "passive"))
      (node (ref "Q9") (pin "3") (pinfunction "D_3") (pintype "passive"))
      (node (ref "SP7") (pin "2") (pintype "passive"))
    )
    (net (code "31") (name "Net-(D8-A2)") (class "Default")
      (node (ref "D8") (pin "2") (pinfunction "A2_2") (pintype "passive"))
      (node (ref "J4") (pin "3") (pinfunction "3_3") (pintype "passive"))
      (node (ref "Q10") (pin "3") (pinfunction "D_3") (pintype "passive"))
      (node (ref "SP6") (pin "2") (pintype "passive"))
    )
    (net (code "32") (name "Net-(D9-A2)") (class "Default")
      (node (ref "D9") (pin "2") (pinfunction "A2_2") (pintype "passive"))
      (node (ref "J4") (pin "4") (pinfunction "4_4") (pintype "passive"))
      (node (ref "Q11") (pin "3") (pinfunction "D_3") (pintype "passive"))
      (node (ref "SP5") (pin "2") (pintype "passive"))
    )
    (net (code "33") (name "Net-(D10-A2)") (class "Default")
      (node (ref "D10") (pin "2") (pinfunction "A2_2") (pintype "passive"))
      (node (ref "J4") (pin "5") (pinfunction "5_5") (pintype "passive"))
      (node (ref "Q12") (pin "3") (pinfunction "D_3") (pintype "passive"))
      (node (ref "SP4") (pin "2") (pintype "passive"))
    )
    (net (code "34") (name "Net-(D11-A2)") (class "Default")
      (node (ref "D11") (pin "2") (pinfunction "A2_2") (pintype "passive"))
      (node (ref "J4") (pin "6") (pinfunction "6_6") (pintype "passive"))
      (node (ref "Q13") (pin "3") (pinfunction "D_3") (pintype "passive"))
      (node (ref "SP3") (pin "2") (pintype "passive"))
    )
    (net (code "35") (name "Net-(D12-A2)") (class "Default")
      (node (ref "D12") (pin "2") (pinfunction "A2_2") (pintype "passive"))
      (node (ref "J4") (pin "7") (pinfunction "7_7") (pintype "passive"))
      (node (ref "Q14") (pin "3") (pinfunction "D_3") (pintype "passive"))
      (node (ref "SP2") (pin "2") (pintype "passive"))
    )
    (net (code "36") (name "Net-(D13-A2)") (class "Default")
      (node (ref "D13") (pin "2") (pinfunction "A2_2") (pintype "passive"))
      (node (ref "J4") (pin "8") (pinfunction "8_8") (pintype "passive"))
      (node (ref "Q15") (pin "3") (pinfunction "D_3") (pintype "passive"))
      (node (ref "SP1") (pin "2") (pintype "passive"))
    )
    (net (code "37") (name "Net-(J3-Pad2)") (class "Default")
      (node (ref "J3") (pin "2") (pinfunction "2_2") (pintype "passive"))
      (node (ref "R45") (pin "2") (pintype "passive"))
    )
    (net (code "38") (name "Net-(J3-Pad3)") (class "Default")
      (node (ref "J3") (pin "3") (pinfunction "3_3") (pintype "passive"))
      (node (ref "R44") (pin "2") (pintype "passive"))
    )
    (net (code "39") (name "Net-(LD3-A)") (class "Default")
      (node (ref "LD3") (pin "1") (pinfunction "A_1") (pintype "passive"))
      (node (ref "R39") (pin "1") (pintype "passive"))
    )
    (net (code "40") (name "Net-(Q4-D)") (class "Default")
      (node (ref "C19") (pin "1") (pintype "passive"))
      (node (ref "C20") (pin "1") (pintype "passive"))
      (node (ref "L2") (pin "2") (pintype "passive"))
      (node (ref "Q4") (pin "3") (pinfunction "D_3") (pintype "passive"))
      (node (ref "U2") (pin "2") (pinfunction "VIN_2") (pintype "passive"))
      (node (ref "U2") (pin "3") (pinfunction "EN_3") (pintype "passive"))
    )
    (net (code "41") (name "Net-(Q4-G)") (class "Default")
      (node (ref "Q4") (pin "1") (pinfunction "G_1") (pintype "passive"))
      (node (ref "R24") (pin "1") (pintype "passive"))
      (node (ref "R26") (pin "2") (pintype "passive"))
    )
    (net (code "42") (name "Net-(Q5-D)") (class "Default")
      (node (ref "Q5") (pin "3") (pinfunction "D_3") (pintype "passive"))
      (node (ref "R26") (pin "1") (pintype "passive"))
    )
    (net (code "43") (name "Net-(Q6-G)") (class "Default")
      (node (ref "Q6") (pin "1") (pinfunction "G_1") (pintype "passive"))
      (node (ref "R29") (pin "2") (pintype "passive"))
      (node (ref "R30") (pin "1") (pintype "passive"))
    )
    (net (code "44") (name "Net-(Q7-D)") (class "Default")
      (node (ref "Q7") (pin "3") (pinfunction "D_3") (pintype "passive"))
      (node (ref "R30") (pin "2") (pintype "passive"))
    )
    (net (code "45") (name "Net-(Q8-G)") (class "Default")
      (node (ref "Q8") (pin "1") (pinfunction "G_1") (pintype "passive"))
      (node (ref "R33") (pin "2") (pintype "passive"))
      (node (ref "R34") (pin "1") (pintype "passive"))
    )
    (net (code "46") (name "Net-(Q9-G)") (class "Default")
      (node (ref "Q9") (pin "1") (pinfunction "G_1") (pintype "passive"))
      (node (ref "R35") (pin "2") (pintype "passive"))
      (node (ref "R36") (pin "1") (pintype "passive"))
    )
    (net (code "47") (name "Net-(Q10-G)") (class "Default")
      (node (ref "Q10") (pin "1") (pinfunction "G_1") (pintype "passive"))
      (node (ref "R37") (pin "2") (pintype "passive"))
      (node (ref "R38") (pin "1") (pintype "passive"))
    )
    (net (code "48") (name "Net-(Q11-G)") (class "Default")
      (node (ref "Q11") (pin "1") (pinfunction "G_1") (pintype "passive"))
      (node (ref "R40") (pin "2") (pintype "passive"))
      (node (ref "R41") (pin "1") (pintype "passive"))
    )
    (net (code "49") (name "Net-(Q12-G)") (class "Default")
      (node (ref "Q12") (pin "1") (pinfunction "G_1") (pintype "passive"))
      (node (ref "R42") (pin "2") (pintype "passive"))
      (node (ref "R43") (pin "1") (pintype "passive"))
    )
    (net (code "50") (name "Net-(Q13-G)") (class "Default")
      (node (ref "Q13") (pin "1") (pinfunction "G_1") (pintype "passive"))
      (node (ref "R46") (pin "2") (pintype "passive"))
      (node (ref "R47") (pin "1") (pintype "passive"))
    )
    (net (code "51") (name "Net-(Q14-G)") (class "Default")
      (node (ref "Q14") (pin "1") (pinfunction "G_1") (pintype "passive"))
      (node (ref "R50") (pin "2") (pintype "passive"))
      (node (ref "R51") (pin "1") (pintype "passive"))
    )
    (net (code "52") (name "Net-(Q15-G)") (class "Default")
      (node (ref "Q15") (pin "1") (pinfunction "G_1") (pintype "passive"))
      (node (ref "R52") (pin "2") (pintype "passive"))
      (node (ref "R53") (pin "1") (pintype "passive"))
    )
    (net (code "53") (name "Net-(U2-COMP)") (class "Default")
      (node (ref "C17") (pin "1") (pintype "passive"))
      (node (ref "R23") (pin "2") (pintype "passive"))
      (node (ref "U2") (pin "7") (pinfunction "COMP_7") (pintype "passive"))
    )
    (net (code "54") (name "Net-(U2-FB)") (class "Default")
      (node (ref "R27") (pin "2") (pintype "passive"))
      (node (ref "R28") (pin "1") (pintype "passive"))
      (node (ref "U2") (pin "8") (pinfunction "FB_8") (pintype "passive"))
    )
    (net (code "55") (name "Net-(U2-FREQ)") (class "Default")
      (node (ref "R22") (pin "2") (pintype "passive"))
      (node (ref "U2") (pin "9") (pinfunction "FREQ_9") (pintype "passive"))
    )
    (net (code "56") (name "Net-(U2-SS)") (class "Default")
      (node (ref "C18") (pin "1") (pintype "passive"))
      (node (ref "U2") (pin "4") (pinfunction "SS_4") (pintype "power_in"))
    )
    (net (code "57") (name "Net-(U3-BST)") (class "Default")
      (node (ref "C23") (pin "1") (pintype "passive"))
      (node (ref "U3") (pin "6") (pinfunction "BST_6") (pintype "passive"))
    )
    (net (code "58") (name "Net-(U3-SW)") (class "Default")
      (node (ref "C23") (pin "2") (pintype "passive"))
      (node (ref "L3") (pin "1") (pintype "passive"))
      (node (ref "U3") (pin "5") (pinfunction "SW_5") (pintype "passive"))
    )
    (net (code "59") (name "Net-(U4-P10)") (class "Default")
      (node (ref "R48") (pin "1") (pintype "passive"))
      (node (ref "U4") (pin "13") (pinfunction "P10_13") (pintype "passive"))
    )
    (net (code "60") (name "Net-(U4-P11)") (class "Default")
      (node (ref "R49") (pin "1") (pintype "passive"))
      (node (ref "U4") (pin "14") (pinfunction "P11_14") (pintype "passive"))
    )
    (net (code "61") (name "VBAT") (class "Default")
      (node (ref "C25") (pin "1") (pintype "passive"))
      (node (ref "D3") (pin "2") (pinfunction "K_2") (pintype "passive"))
      (node (ref "D4") (pin "1") (pinfunction "A_1") (pintype "passive"))
      (node (ref "Q4") (pin "2") (pinfunction "S_2") (pintype "passive"))
      (node (ref "R24") (pin "2") (pintype "passive"))
      (node (ref "U3") (pin "2") (pinfunction "EN_2") (pintype "passive"))
      (node (ref "U3") (pin "3") (pinfunction "VIN_3") (pintype "passive"))
    )
    (net (code "62") (name "unconnected-(Jext-Pad1)") (class "Default")
      (node (ref "Jext") (pin "1") (pinfunction "1_1") (pintype "passive"))
    )
    (net (code "63") (name "unconnected-(Jext-Pad2)") (class "Default")
      (node (ref "Jext") (pin "2") (pinfunction "2_2") (pintype "passive"))
    )
    (net (code "64") (name "unconnected-(Jext-Pad5)") (class "Default")
      (node (ref "Jext") (pin "5") (pinfunction "5_5") (pintype "passive"))
    )
    (net (code "65") (name "unconnected-(Jext-Pad6)") (class "Default")
      (node (ref "Jext") (pin "6") (pinfunction "6_6") (pintype "passive"))
    )
  )
)
